# PAGE14.net
KiCad netlist of a schematic drawn in Altium Designer
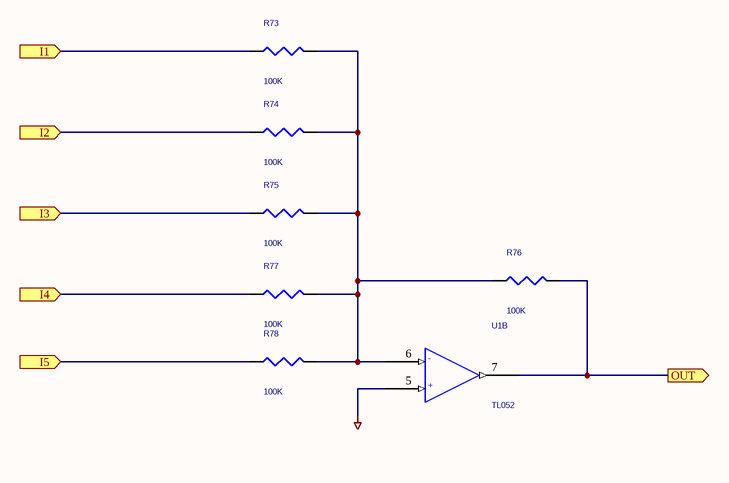
[diagram p0: PAGE14.SchDoc]

(export (version "E")
  (design (tool "Eeschema 10.0.6"))
  (components
    (comp (ref "R73") (value "100K") (libsource (lib "*") (part "R_Dup1")))
    (comp (ref "R74") (value "100K") (libsource (lib "*") (part "R_Dup1")))
    (comp (ref "R75") (value "100K") (libsource (lib "*") (part "R_Dup1")))
    (comp (ref "R76") (value "100K") (libsource (lib "*") (part "R_Dup1")))
    (comp (ref "R77") (value "100K") (libsource (lib "*") (part "R_Dup1")))
    (comp (ref "R78") (value "100K") (libsource (lib "*") (part "R_Dup1")))
    (comp (ref "U1") (value "TL052") (footprint "DIP8") (libsource (lib "*") (part "GEN DUAL OPAMP-H")))
  )
  (nets
    (net (code "1") (name "/I1") (class "Default")
      (node (ref "R73") (pin "1") (pinfunction "1_1") (pintype "passive"))
    )
    (net (code "2") (name "/I2") (class "Default")
      (node (ref "R74") (pin "1") (pinfunction "1_1") (pintype "passive"))
    )
    (net (code "3") (name "/I3") (class "Default")
      (node (ref "R75") (pin "1") (pinfunction "1_1") (pintype "passive"))
    )
    (net (code "4") (name "/I4") (class "Default")
      (node (ref "R77") (pin "1") (pinfunction "1_1") (pintype "passive"))
    )
    (net (code "5") (name "/I5") (class "Default")
      (node (ref "R78") (pin "1") (pinfunction "1_1") (pintype "passive"))
    )
    (net (code "6") (name "/OUT") (class "Default")
      (node (ref "R76") (pin "2") (pinfunction "2_2") (pintype "passive"))
      (node (ref "U1") (pin "7") (pinfunction "OUT_7") (pintype "output"))
    )
    (net (code "7") (name "AGND") (class "Default")
      (node (ref "U1") (pin "5") (pinfunction "+_5") (pintype "input"))
    )
    (net (code "8") (name "Net-(U1B--)") (class "Default")
      (node (ref "R73") (pin "2") (pinfunction "2_2") (pintype "passive"))
      (node (ref "R74") (pin "2") (pinfunction "2_2") (pintype "passive"))
      (node (ref "R75") (pin "2") (pinfunction "2_2") (pintype "passive"))
      (node (ref "R76") (pin "1") (pinfunction "1_1") (pintype "passive"))
      (node (ref "R77") (pin "2") (pinfunction "2_2") (pintype "passive"))
      (node (ref "R78") (pin "2") (pinfunction "2_2") (pintype "passive"))
      (node (ref "U1") (pin "6") (pinfunction "-_6") (pintype "input"))
    )
  )
)
